# hybrid.net
KiCad netlist of a schematic drawn in EAGLE
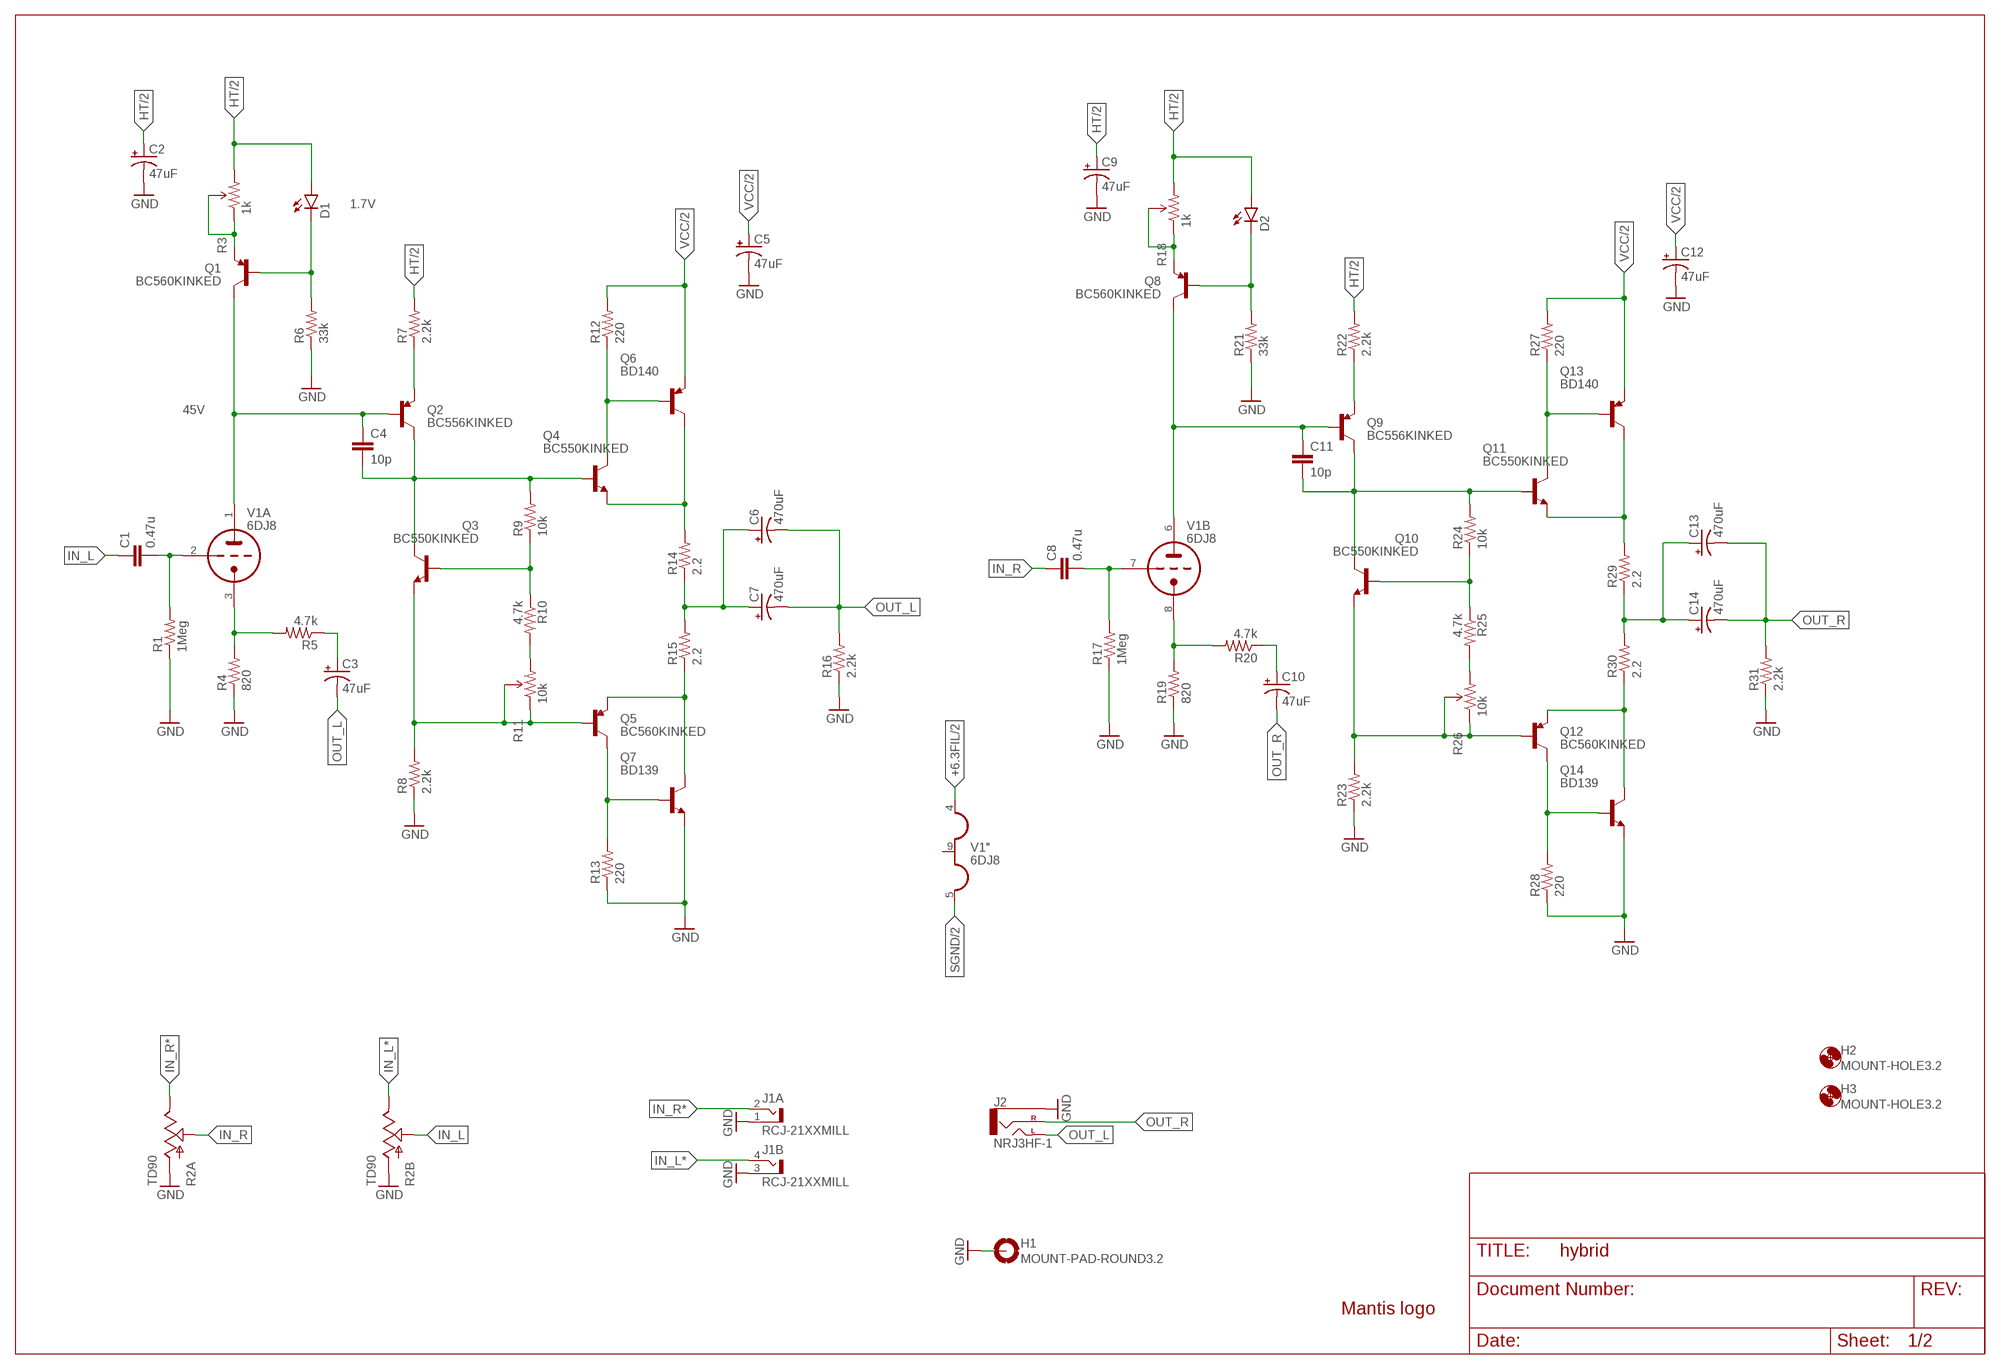
[diagram p0: schematic, sheet 1]
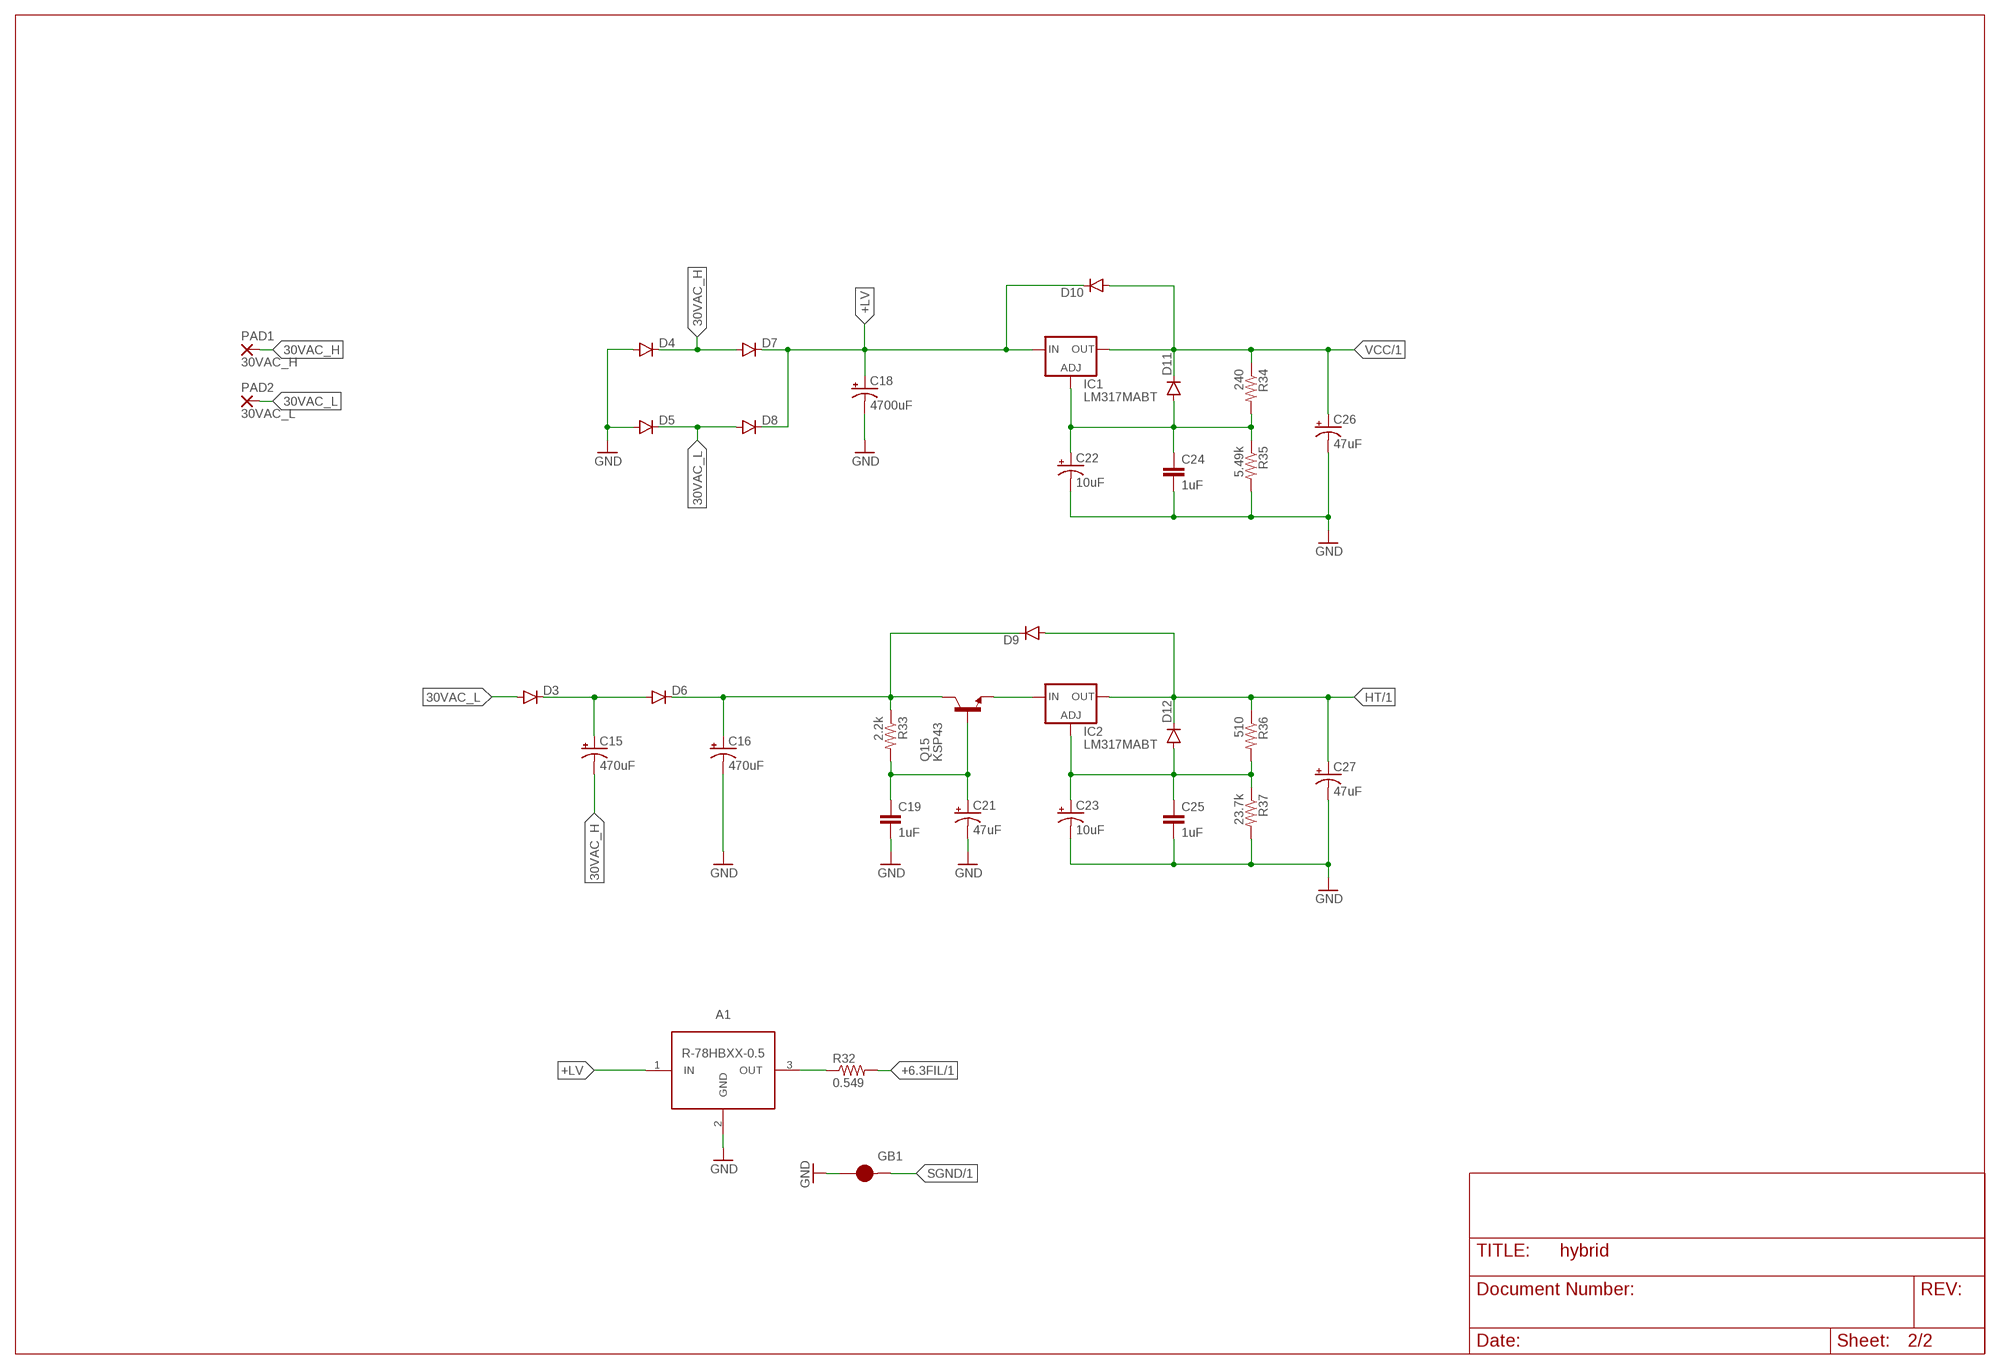
[diagram p1: schematic, sheet 2]

(export (version "E")
  (design (tool "Eeschema 10.0.6"))
  (components
    (comp (ref "A1")
      (value "R-78HBXX-0.5")
      (footprint "eagle-import:R-78HB")
      (libsource (lib "eagle-import") (part "R-78HBXX-0.5"))
    )
    (comp (ref "C15")
      (value "470uF")
      (footprint "eagle-import:CPOL-RADIAL-16_7.5")
      (libsource (lib "eagle-import") (part "CAP_POLPTH-16/7.5"))
    )
    (comp (ref "C16")
      (value "470uF")
      (footprint "eagle-import:CPOL-RADIAL-16_7.5")
      (libsource (lib "eagle-import") (part "CAP_POLPTH-16/7.5"))
    )
    (comp (ref "C18")
      (value "4700uF")
      (footprint "eagle-import:CPOL-RADIAL-22_10")
      (libsource (lib "eagle-import") (part "CAP_POLPTH-22/10"))
    )
    (comp (ref "C19")
      (value "1uF")
      (footprint "eagle-import:CAP-PTH-SMALL")
      (libsource (lib "eagle-import") (part "CAPPTH"))
    )
    (comp (ref "C21")
      (value "47uF")
      (footprint "eagle-import:CPOL-RADIAL-12_5")
      (libsource (lib "eagle-import") (part "CAP_POLPTH-12/5"))
    )
    (comp (ref "C22")
      (value "10uF")
      (footprint "eagle-import:CPOL-RADIAL-5_2.5")
      (libsource (lib "eagle-import") (part "CAP_POLPTH-5/2.5"))
    )
    (comp (ref "C23")
      (value "10uF")
      (footprint "eagle-import:CPOL-RADIAL-6.5_2.5")
      (libsource (lib "eagle-import") (part "CAP_POLPTH-6.5/2.5"))
    )
    (comp (ref "C24")
      (value "1uF")
      (footprint "eagle-import:CAP-PTH-SMALL")
      (libsource (lib "eagle-import") (part "CAPPTH"))
    )
    (comp (ref "C25")
      (value "1uF")
      (footprint "eagle-import:CAP-PTH-SMALL")
      (libsource (lib "eagle-import") (part "CAPPTH"))
    )
    (comp (ref "C26")
      (value "47uF")
      (footprint "eagle-import:CPOL-RADIAL-8_3.5")
      (libsource (lib "eagle-import") (part "CAP_POLPTH-8/3.5"))
    )
    (comp (ref "C27")
      (value "47uF")
      (footprint "eagle-import:CPOL-RADIAL-8_3.5")
      (libsource (lib "eagle-import") (part "CAP_POLPTH-8/3.5"))
    )
    (comp (ref "D3")
      (value "DIODEPTH")
      (footprint "eagle-import:DIODE-1N4001")
      (libsource (lib "eagle-import") (part "DIODEPTH"))
    )
    (comp (ref "D4")
      (value "DIODEPTH")
      (footprint "eagle-import:DIODE-1N4001")
      (libsource (lib "eagle-import") (part "DIODEPTH"))
    )
    (comp (ref "D5")
      (value "DIODEPTH")
      (footprint "eagle-import:DIODE-1N4001")
      (libsource (lib "eagle-import") (part "DIODEPTH"))
    )
    (comp (ref "D6")
      (value "DIODEPTH")
      (footprint "eagle-import:DIODE-1N4001")
      (libsource (lib "eagle-import") (part "DIODEPTH"))
    )
    (comp (ref "D7")
      (value "DIODEPTH")
      (footprint "eagle-import:DIODE-1N4001")
      (libsource (lib "eagle-import") (part "DIODEPTH"))
    )
    (comp (ref "D8")
      (value "DIODEPTH")
      (footprint "eagle-import:DIODE-1N4001")
      (libsource (lib "eagle-import") (part "DIODEPTH"))
    )
    (comp (ref "D9")
      (value "DIODEPTH")
      (footprint "eagle-import:DIODE-1N4001")
      (libsource (lib "eagle-import") (part "DIODEPTH"))
    )
    (comp (ref "D10")
      (value "DIODEPTH")
      (footprint "eagle-import:DIODE-1N4001")
      (libsource (lib "eagle-import") (part "DIODEPTH"))
    )
    (comp (ref "D11")
      (value "DIODEPTH")
      (footprint "eagle-import:DIODE-1N4001")
      (libsource (lib "eagle-import") (part "DIODEPTH"))
    )
    (comp (ref "D12")
      (value "DIODEPTH")
      (footprint "eagle-import:DIODE-1N4001")
      (libsource (lib "eagle-import") (part "DIODEPTH"))
    )
    (comp (ref "GB1")
      (value "COPPER-BRIDGESM")
      (footprint "eagle-import:COPPER-BRIDGE-SM")
      (libsource (lib "eagle-import") (part "COPPER-BRIDGESM"))
    )
    (comp (ref "IC1")
      (value "LM317MABT")
      (footprint "eagle-import:TO220L1")
      (libsource (lib "eagle-import") (part "LM317?MABT"))
    )
    (comp (ref "IC2")
      (value "LM317MABT")
      (footprint "eagle-import:TO220L1")
      (libsource (lib "eagle-import") (part "LM317?MABT"))
    )
    (comp (ref "PAD1")
      (value "30VAC_H")
      (footprint "eagle-import:3,81_1,4")
      (libsource (lib "eagle-import") (part "3,81/1,4"))
    )
    (comp (ref "PAD2")
      (value "30VAC_L")
      (footprint "eagle-import:3,81_1,4")
      (libsource (lib "eagle-import") (part "3,81/1,4"))
    )
    (comp (ref "Q15")
      (value "KSP43")
      (footprint "eagle-import:TO-92")
      (libsource (lib "eagle-import") (part "KSP43"))
    )
    (comp (ref "R32")
      (value "0.549")
      (footprint "eagle-import:AXIAL-0.5")
      (libsource (lib "eagle-import") (part "my-res_RESISTORPTH-1/2W"))
    )
    (comp (ref "R33")
      (value "2.2k")
      (footprint "eagle-import:AXIAL-0.4")
      (libsource (lib "eagle-import") (part "RESISTORPTH-1/4W"))
    )
    (comp (ref "R34")
      (value "240")
      (footprint "eagle-import:AXIAL-0.4")
      (libsource (lib "eagle-import") (part "RESISTORPTH-1/4W"))
    )
    (comp (ref "R35")
      (value "5.49k")
      (footprint "eagle-import:AXIAL-0.4")
      (libsource (lib "eagle-import") (part "RESISTORPTH-1/4W"))
    )
    (comp (ref "R36")
      (value "510")
      (footprint "eagle-import:AXIAL-0.4")
      (libsource (lib "eagle-import") (part "RESISTORPTH-1/4W"))
    )
    (comp (ref "R37")
      (value "23.7k")
      (footprint "eagle-import:AXIAL-0.4")
      (libsource (lib "eagle-import") (part "RESISTORPTH-1/4W"))
    )
    (comp (ref "C1")
      (value "0.47u")
      (footprint "eagle-import:C5B3.5")
      (libsource (lib "eagle-import") (part "C5/3.5"))
    )
    (comp (ref "C2")
      (value "47uF")
      (footprint "eagle-import:CPOL-RADIAL-8_3.5")
      (libsource (lib "eagle-import") (part "CAP_POLPTH-8/3.5"))
    )
    (comp (ref "C3")
      (value "47uF")
      (footprint "eagle-import:CPOL-RADIAL-8_3.5")
      (libsource (lib "eagle-import") (part "CAP_POLPTH-8/3.5"))
    )
    (comp (ref "C4")
      (value "10p")
      (footprint "eagle-import:CAP-PTH-SMALL")
      (libsource (lib "eagle-import") (part "CAPPTH"))
    )
    (comp (ref "C5")
      (value "47uF")
      (footprint "eagle-import:CPOL-RADIAL-8_3.5")
      (libsource (lib "eagle-import") (part "CAP_POLPTH-8/3.5"))
    )
    (comp (ref "C6")
      (value "470uF")
      (footprint "eagle-import:CPOL-RADIAL-12_5")
      (libsource (lib "eagle-import") (part "CAP_POLPTH-12/5"))
    )
    (comp (ref "C7")
      (value "470uF")
      (footprint "eagle-import:CPOL-RADIAL-12_5")
      (libsource (lib "eagle-import") (part "CAP_POLPTH-12/5"))
    )
    (comp (ref "C8")
      (value "0.47u")
      (footprint "eagle-import:C5B3.5")
      (libsource (lib "eagle-import") (part "C5/3.5"))
    )
    (comp (ref "C9")
      (value "47uF")
      (footprint "eagle-import:CPOL-RADIAL-8_3.5")
      (libsource (lib "eagle-import") (part "CAP_POLPTH-8/3.5"))
    )
    (comp (ref "C10")
      (value "47uF")
      (footprint "eagle-import:CPOL-RADIAL-8_3.5")
      (libsource (lib "eagle-import") (part "CAP_POLPTH-8/3.5"))
    )
    (comp (ref "C11")
      (value "10p")
      (footprint "eagle-import:CAP-PTH-SMALL")
      (libsource (lib "eagle-import") (part "CAPPTH"))
    )
    (comp (ref "C12")
      (value "47uF")
      (footprint "eagle-import:CPOL-RADIAL-8_3.5")
      (libsource (lib "eagle-import") (part "CAP_POLPTH-8/3.5"))
    )
    (comp (ref "C13")
      (value "470uF")
      (footprint "eagle-import:CPOL-RADIAL-12_5")
      (libsource (lib "eagle-import") (part "CAP_POLPTH-12/5"))
    )
    (comp (ref "C14")
      (value "470uF")
      (footprint "eagle-import:CPOL-RADIAL-12_5")
      (libsource (lib "eagle-import") (part "CAP_POLPTH-12/5"))
    )
    (comp (ref "D1")
      (value "LED3MM")
      (footprint "eagle-import:LED3MM")
      (libsource (lib "eagle-import") (part "LED3MM"))
    )
    (comp (ref "D2")
      (value "LED3MM")
      (footprint "eagle-import:LED3MM")
      (libsource (lib "eagle-import") (part "LED3MM"))
    )
    (comp (ref "H1")
      (value "MOUNT-PAD-ROUND3.2")
      (footprint "eagle-import:3,2-PAD")
      (libsource (lib "eagle-import") (part "MOUNT-PAD-ROUND3.2"))
    )
    (comp (ref "H2")
      (value "MOUNT-HOLE3.2")
      (footprint "eagle-import:3,2")
      (libsource (lib "eagle-import") (part "MOUNT-HOLE3.2"))
    )
    (comp (ref "H3")
      (value "MOUNT-HOLE3.2")
      (footprint "eagle-import:3,2")
      (libsource (lib "eagle-import") (part "MOUNT-HOLE3.2"))
    )
    (comp (ref "J1")
      (value "RCJ-21XXMILL")
      (footprint "eagle-import:RCJ-21-MILL")
      (libsource (lib "eagle-import") (part "RCJ-21XXMILL"))
    )
    (comp (ref "J2")
      (value "NRJ3HF-1")
      (footprint "eagle-import:NRJ3HF")
      (libsource (lib "eagle-import") (part "NRJ3HF-1"))
    )
    (comp (ref "LOGO1")
      (value "LOGO-MANTIS")
      (footprint "eagle-import:LOGO-MANTIS")
      (libsource (lib "eagle-import") (part "LOGO-MANTIS"))
    )
    (comp (ref "Q1")
      (value "BC560KINKED")
      (footprint "eagle-import:TO92-BENT")
      (libsource (lib "eagle-import") (part "BC560KINKED"))
    )
    (comp (ref "Q2")
      (value "BC556KINKED")
      (footprint "eagle-import:TO92-BENT")
      (libsource (lib "eagle-import") (part "BC556KINKED"))
    )
    (comp (ref "Q3")
      (value "BC550KINKED")
      (footprint "eagle-import:TO92-BENT")
      (libsource (lib "eagle-import") (part "BC550KINKED"))
    )
    (comp (ref "Q4")
      (value "BC550KINKED")
      (footprint "eagle-import:TO92-BENT")
      (libsource (lib "eagle-import") (part "BC550KINKED"))
    )
    (comp (ref "Q5")
      (value "BC560KINKED")
      (footprint "eagle-import:TO92-BENT")
      (libsource (lib "eagle-import") (part "BC560KINKED"))
    )
    (comp (ref "Q6")
      (value "BD140")
      (footprint "eagle-import:TO126")
      (libsource (lib "eagle-import") (part "BD140"))
    )
    (comp (ref "Q7")
      (value "BD139")
      (footprint "eagle-import:TO126")
      (libsource (lib "eagle-import") (part "BD139"))
    )
    (comp (ref "Q8")
      (value "BC560KINKED")
      (footprint "eagle-import:TO92-BENT")
      (libsource (lib "eagle-import") (part "BC560KINKED"))
    )
    (comp (ref "Q9")
      (value "BC556KINKED")
      (footprint "eagle-import:TO92-BENT")
      (libsource (lib "eagle-import") (part "BC556KINKED"))
    )
    (comp (ref "Q10")
      (value "BC550KINKED")
      (footprint "eagle-import:TO92-BENT")
      (libsource (lib "eagle-import") (part "BC550KINKED"))
    )
    (comp (ref "Q11")
      (value "BC550KINKED")
      (footprint "eagle-import:TO92-BENT")
      (libsource (lib "eagle-import") (part "BC550KINKED"))
    )
    (comp (ref "Q12")
      (value "BC560KINKED")
      (footprint "eagle-import:TO92-BENT")
      (libsource (lib "eagle-import") (part "BC560KINKED"))
    )
    (comp (ref "Q13")
      (value "BD140")
      (footprint "eagle-import:TO126")
      (libsource (lib "eagle-import") (part "BD140"))
    )
    (comp (ref "Q14")
      (value "BD139")
      (footprint "eagle-import:TO126")
      (libsource (lib "eagle-import") (part "BD139"))
    )
    (comp (ref "R1")
      (value "1Meg")
      (footprint "eagle-import:AXIAL-0.4")
      (libsource (lib "eagle-import") (part "RESISTORPTH-1/4W"))
    )
    (comp (ref "R2")
      (value "TD90")
      (footprint "eagle-import:PTD902")
      (libsource (lib "eagle-import") (part "TD90"))
    )
    (comp (ref "R3")
      (value "1k")
      (footprint "eagle-import:3362U-2")
      (libsource (lib "eagle-import") (part "TRIMPOT3362U-2"))
    )
    (comp (ref "R4")
      (value "820")
      (footprint "eagle-import:AXIAL-0.4")
      (libsource (lib "eagle-import") (part "RESISTORPTH-1/4W"))
    )
    (comp (ref "R5")
      (value "4.7k")
      (footprint "eagle-import:AXIAL-0.4")
      (libsource (lib "eagle-import") (part "RESISTORPTH-1/4W"))
    )
    (comp (ref "R6")
      (value "33k")
      (footprint "eagle-import:AXIAL-0.4")
      (libsource (lib "eagle-import") (part "RESISTORPTH-1/4W"))
    )
    (comp (ref "R7")
      (value "2.2k")
      (footprint "eagle-import:AXIAL-0.4")
      (libsource (lib "eagle-import") (part "RESISTORPTH-1/4W"))
    )
    (comp (ref "R8")
      (value "2.2k")
      (footprint "eagle-import:AXIAL-0.4")
      (libsource (lib "eagle-import") (part "RESISTORPTH-1/4W"))
    )
    (comp (ref "R9")
      (value "10k")
      (footprint "eagle-import:AXIAL-0.4")
      (libsource (lib "eagle-import") (part "RESISTORPTH-1/4W"))
    )
    (comp (ref "R10")
      (value "4.7k")
      (footprint "eagle-import:AXIAL-0.4")
      (libsource (lib "eagle-import") (part "RESISTORPTH-1/4W"))
    )
    (comp (ref "R11")
      (value "10k")
      (footprint "eagle-import:3362U-2")
      (libsource (lib "eagle-import") (part "TRIMPOT3362U-2"))
    )
    (comp (ref "R12")
      (value "220")
      (footprint "eagle-import:AXIAL-0.4")
      (libsource (lib "eagle-import") (part "RESISTORPTH-1/4W"))
    )
    (comp (ref "R13")
      (value "220")
      (footprint "eagle-import:AXIAL-0.4")
      (libsource (lib "eagle-import") (part "RESISTORPTH-1/4W"))
    )
    (comp (ref "R14")
      (value "2.2")
      (footprint "eagle-import:AXIAL-0.5")
      (libsource (lib "eagle-import") (part "RESISTORPTH-1/2W"))
    )
    (comp (ref "R15")
      (value "2.2")
      (footprint "eagle-import:AXIAL-0.5")
      (libsource (lib "eagle-import") (part "RESISTORPTH-1/2W"))
    )
    (comp (ref "R16")
      (value "2.2k")
      (footprint "eagle-import:AXIAL-0.4")
      (libsource (lib "eagle-import") (part "RESISTORPTH-1/4W"))
    )
    (comp (ref "R17")
      (value "1Meg")
      (footprint "eagle-import:AXIAL-0.4")
      (libsource (lib "eagle-import") (part "RESISTORPTH-1/4W"))
    )
    (comp (ref "R18")
      (value "1k")
      (footprint "eagle-import:3362U-2")
      (libsource (lib "eagle-import") (part "TRIMPOT3362U-2"))
    )
    (comp (ref "R19")
      (value "820")
      (footprint "eagle-import:AXIAL-0.4")
      (libsource (lib "eagle-import") (part "RESISTORPTH-1/4W"))
    )
    (comp (ref "R20")
      (value "4.7k")
      (footprint "eagle-import:AXIAL-0.4")
      (libsource (lib "eagle-import") (part "RESISTORPTH-1/4W"))
    )
    (comp (ref "R21")
      (value "33k")
      (footprint "eagle-import:AXIAL-0.4")
      (libsource (lib "eagle-import") (part "RESISTORPTH-1/4W"))
    )
    (comp (ref "R22")
      (value "2.2k")
      (footprint "eagle-import:AXIAL-0.4")
      (libsource (lib "eagle-import") (part "RESISTORPTH-1/4W"))
    )
    (comp (ref "R23")
      (value "2.2k")
      (footprint "eagle-import:AXIAL-0.4")
      (libsource (lib "eagle-import") (part "RESISTORPTH-1/4W"))
    )
    (comp (ref "R24")
      (value "10k")
      (footprint "eagle-import:AXIAL-0.4")
      (libsource (lib "eagle-import") (part "RESISTORPTH-1/4W"))
    )
    (comp (ref "R25")
      (value "4.7k")
      (footprint "eagle-import:AXIAL-0.4")
      (libsource (lib "eagle-import") (part "RESISTORPTH-1/4W"))
    )
    (comp (ref "R26")
      (value "10k")
      (footprint "eagle-import:3362U-2")
      (libsource (lib "eagle-import") (part "TRIMPOT3362U-2"))
    )
    (comp (ref "R27")
      (value "220")
      (footprint "eagle-import:AXIAL-0.4")
      (libsource (lib "eagle-import") (part "RESISTORPTH-1/4W"))
    )
    (comp (ref "R28")
      (value "220")
      (footprint "eagle-import:AXIAL-0.4")
      (libsource (lib "eagle-import") (part "RESISTORPTH-1/4W"))
    )
    (comp (ref "R29")
      (value "2.2")
      (footprint "eagle-import:AXIAL-0.5")
      (libsource (lib "eagle-import") (part "RESISTORPTH-1/2W"))
    )
    (comp (ref "R30")
      (value "2.2")
      (footprint "eagle-import:AXIAL-0.5")
      (libsource (lib "eagle-import") (part "RESISTORPTH-1/2W"))
    )
    (comp (ref "R31")
      (value "2.2k")
      (footprint "eagle-import:AXIAL-0.4")
      (libsource (lib "eagle-import") (part "RESISTORPTH-1/4W"))
    )
    (comp (ref "V1")
      (value "6DJ8")
      (footprint "eagle-import:NOVAL")
      (libsource (lib "eagle-import") (part "6DJ8-P"))
    )
  )
  (nets
    (net (code "1") (name "+6.3FIL") (class "Default")
      (node (ref "R32") (pin "P$2") (pinfunction "2_P$2") (pintype "passive"))
      (node (ref "V1") (pin "4") (pinfunction "H1_4") (pintype "passive"))
    )
    (net (code "2") (name "+LV") (class "Default")
      (node (ref "A1") (pin "1") (pinfunction "IN_1") (pintype "bidirectional"))
      (node (ref "C18") (pin "1") (pinfunction "+_1") (pintype "passive"))
      (node (ref "D10") (pin "C") (pinfunction "C_C") (pintype "passive"))
      (node (ref "D7") (pin "C") (pinfunction "C_C") (pintype "passive"))
      (node (ref "D8") (pin "C") (pinfunction "C_C") (pintype "passive"))
      (node (ref "IC1") (pin "3") (pinfunction "IN_3") (pintype "input"))
    )
    (net (code "3") (name "30VAC_H") (class "Default")
      (node (ref "C15") (pin "2") (pinfunction "-_2") (pintype "passive"))
      (node (ref "D4") (pin "C") (pinfunction "C_C") (pintype "passive"))
      (node (ref "D7") (pin "A") (pinfunction "A_A") (pintype "passive"))
      (node (ref "PAD1") (pin "1") (pinfunction "P_1") (pintype "passive"))
    )
    (net (code "4") (name "30VAC_L") (class "Default")
      (node (ref "D3") (pin "A") (pinfunction "A_A") (pintype "passive"))
      (node (ref "D5") (pin "C") (pinfunction "C_C") (pintype "passive"))
      (node (ref "D8") (pin "A") (pinfunction "A_A") (pintype "passive"))
      (node (ref "PAD2") (pin "1") (pinfunction "P_1") (pintype "passive"))
    )
    (net (code "5") (name "GND") (class "Default")
      (node (ref "A1") (pin "2") (pinfunction "GND_2") (pintype "bidirectional"))
      (node (ref "C12") (pin "2") (pinfunction "-_2") (pintype "passive"))
      (node (ref "C16") (pin "2") (pinfunction "-_2") (pintype "passive"))
      (node (ref "C18") (pin "2") (pinfunction "-_2") (pintype "passive"))
      (node (ref "C19") (pin "2") (pinfunction "2_2") (pintype "passive"))
      (node (ref "C2") (pin "2") (pinfunction "-_2") (pintype "passive"))
      (node (ref "C21") (pin "-") (pinfunction "-_-") (pintype "passive"))
      (node (ref "C22") (pin "2") (pinfunction "-_2") (pintype "passive"))
      (node (ref "C23") (pin "2") (pinfunction "-_2") (pintype "passive"))
      (node (ref "C24") (pin "2") (pinfunction "2_2") (pintype "passive"))
      (node (ref "C25") (pin "2") (pinfunction "2_2") (pintype "passive"))
      (node (ref "C26") (pin "2") (pinfunction "-_2") (pintype "passive"))
      (node (ref "C27") (pin "2") (pinfunction "-_2") (pintype "passive"))
      (node (ref "C5") (pin "2") (pinfunction "-_2") (pintype "passive"))
      (node (ref "C9") (pin "2") (pinfunction "-_2") (pintype "passive"))
      (node (ref "D4") (pin "A") (pinfunction "A_A") (pintype "passive"))
      (node (ref "D5") (pin "A") (pinfunction "A_A") (pintype "passive"))
      (node (ref "GB1") (pin "1") (pinfunction "1_1") (pintype "passive"))
      (node (ref "H1") (pin "B3,2") (pinfunction "MOUNT_B3,2") (pintype "passive"))
      (node (ref "J1") (pin "1") (pinfunction "S_1") (pintype "passive"))
      (node (ref "J1") (pin "3") (pinfunction "S_3") (pintype "passive"))
      (node (ref "J2") (pin "S") (pinfunction "SLEEVE_S") (pintype "bidirectional"))
      (node (ref "Q14") (pin "1") (pinfunction "E_1") (pintype "passive"))
      (node (ref "Q7") (pin "1") (pinfunction "E_1") (pintype "passive"))
      (node (ref "R1") (pin "P$1") (pinfunction "1_P$1") (pintype "passive"))
      (node (ref "R13") (pin "P$1") (pinfunction "1_P$1") (pintype "passive"))
      (node (ref "R16") (pin "P$1") (pinfunction "1_P$1") (pintype "passive"))
      (node (ref "R17") (pin "P$1") (pinfunction "1_P$1") (pintype "passive"))
      (node (ref "R19") (pin "P$1") (pinfunction "1_P$1") (pintype "passive"))
      (node (ref "R2") (pin "R1.1") (pinfunction "A_R1.1") (pintype "passive"))
      (node (ref "R2") (pin "R2.1") (pinfunction "A_R2.1") (pintype "passive"))
      (node (ref "R21") (pin "P$1") (pinfunction "1_P$1") (pintype "passive"))
      (node (ref "R23") (pin "P$1") (pinfunction "1_P$1") (pintype "passive"))
      (node (ref "R28") (pin "P$1") (pinfunction "1_P$1") (pintype "passive"))
      (node (ref "R31") (pin "P$1") (pinfunction "1_P$1") (pintype "passive"))
      (node (ref "R35") (pin "P$2") (pinfunction "2_P$2") (pintype "passive"))
      (node (ref "R37") (pin "P$2") (pinfunction "2_P$2") (pintype "passive"))
      (node (ref "R4") (pin "P$1") (pinfunction "1_P$1") (pintype "passive"))
      (node (ref "R6") (pin "P$1") (pinfunction "1_P$1") (pintype "passive"))
      (node (ref "R8") (pin "P$1") (pinfunction "1_P$1") (pintype "passive"))
    )
    (net (code "6") (name "HT") (class "Default")
      (node (ref "C2") (pin "1") (pinfunction "+_1") (pintype "passive"))
      (node (ref "C27") (pin "1") (pinfunction "+_1") (pintype "passive"))
      (node (ref "C9") (pin "1") (pinfunction "+_1") (pintype "passive"))
      (node (ref "D1") (pin "A") (pinfunction "A_A") (pintype "passive"))
      (node (ref "D12") (pin "C") (pinfunction "C_C") (pintype "passive"))
      (node (ref "D2") (pin "A") (pinfunction "A_A") (pintype "passive"))
      (node (ref "D9") (pin "A") (pinfunction "A_A") (pintype "passive"))
      (node (ref "IC2") (pin "2") (pinfunction "OUT_2") (pintype "passive"))
      (node (ref "R18") (pin "3") (pinfunction "CW_3") (pintype "passive"))
      (node (ref "R22") (pin "P$2") (pinfunction "2_P$2") (pintype "passive"))
      (node (ref "R3") (pin "3") (pinfunction "CW_3") (pintype "passive"))
      (node (ref "R36") (pin "P$1") (pinfunction "1_P$1") (pintype "passive"))
      (node (ref "R7") (pin "P$2") (pinfunction "2_P$2") (pintype "passive"))
    )
    (net (code "7") (name "IN_L") (class "Default")
      (node (ref "C1") (pin "1") (pinfunction "1_1") (pintype "passive"))
      (node (ref "R2") (pin "R2.2") (pinfunction "S_R2.2") (pintype "passive"))
    )
    (net (code "8") (name "IN_L*") (class "Default")
      (node (ref "J1") (pin "4") (pinfunction "T_4") (pintype "passive"))
      (node (ref "R2") (pin "R2.3") (pinfunction "E_R2.3") (pintype "passive"))
    )
    (net (code "9") (name "IN_R") (class "Default")
      (node (ref "C8") (pin "1") (pinfunction "1_1") (pintype "passive"))
      (node (ref "R2") (pin "R1.2") (pinfunction "S_R1.2") (pintype "passive"))
    )
    (net (code "10") (name "IN_R*") (class "Default")
      (node (ref "J1") (pin "2") (pinfunction "T_2") (pintype "passive"))
      (node (ref "R2") (pin "R1.3") (pinfunction "E_R1.3") (pintype "passive"))
    )
    (net (code "11") (name "Net-(A1-OUT)") (class "Default")
      (node (ref "A1") (pin "3") (pinfunction "OUT_3") (pintype "bidirectional"))
      (node (ref "R32") (pin "P$1") (pinfunction "1_P$1") (pintype "passive"))
    )
    (net (code "12") (name "Net-(C3-+)") (class "Default")
      (node (ref "C3") (pin "1") (pinfunction "+_1") (pintype "passive"))
      (node (ref "R5") (pin "P$1") (pinfunction "1_P$1") (pintype "passive"))
    )
    (net (code "13") (name "Net-(C10-+)") (class "Default")
      (node (ref "C10") (pin "1") (pinfunction "+_1") (pintype "passive"))
      (node (ref "R20") (pin "P$1") (pinfunction "1_P$1") (pintype "passive"))
    )
    (net (code "14") (name "Net-(C15-+)") (class "Default")
      (node (ref "C15") (pin "1") (pinfunction "+_1") (pintype "passive"))
      (node (ref "D3") (pin "C") (pinfunction "C_C") (pintype "passive"))
      (node (ref "D6") (pin "A") (pinfunction "A_A") (pintype "passive"))
    )
    (net (code "15") (name "Net-(C16-+)") (class "Default")
      (node (ref "C16") (pin "1") (pinfunction "+_1") (pintype "passive"))
      (node (ref "D6") (pin "C") (pinfunction "C_C") (pintype "passive"))
      (node (ref "D9") (pin "C") (pinfunction "C_C") (pintype "passive"))
      (node (ref "Q15") (pin "3") (pinfunction "C_3") (pintype "passive"))
      (node (ref "R33") (pin "P$1") (pinfunction "1_P$1") (pintype "passive"))
    )
    (net (code "16") (name "Net-(C22-+)") (class "Default")
      (node (ref "C22") (pin "1") (pinfunction "+_1") (pintype "passive"))
      (node (ref "C24") (pin "1") (pinfunction "1_1") (pintype "passive"))
      (node (ref "D11") (pin "A") (pinfunction "A_A") (pintype "passive"))
      (node (ref "IC1") (pin "1") (pinfunction "ADJ_1") (pintype "input"))
      (node (ref "R34") (pin "P$2") (pinfunction "2_P$2") (pintype "passive"))
      (node (ref "R35") (pin "P$1") (pinfunction "1_P$1") (pintype "passive"))
    )
    (net (code "17") (name "Net-(C23-+)") (class "Default")
      (node (ref "C23") (pin "1") (pinfunction "+_1") (pintype "passive"))
      (node (ref "C25") (pin "1") (pinfunction "1_1") (pintype "passive"))
      (node (ref "D12") (pin "A") (pinfunction "A_A") (pintype "passive"))
      (node (ref "IC2") (pin "1") (pinfunction "ADJ_1") (pintype "input"))
      (node (ref "R36") (pin "P$2") (pinfunction "2_P$2") (pintype "passive"))
      (node (ref "R37") (pin "P$1") (pinfunction "1_P$1") (pintype "passive"))
    )
    (net (code "18") (name "Net-(D1-C)") (class "Default")
      (node (ref "D1") (pin "K") (pinfunction "C_K") (pintype "passive"))
      (node (ref "Q1") (pin "2") (pinfunction "B_2") (pintype "passive"))
      (node (ref "R6") (pin "P$2") (pinfunction "2_P$2") (pintype "passive"))
    )
    (net (code "19") (name "Net-(D2-C)") (class "Default")
      (node (ref "D2") (pin "K") (pinfunction "C_K") (pintype "passive"))
      (node (ref "Q8") (pin "2") (pinfunction "B_2") (pintype "passive"))
      (node (ref "R21") (pin "P$2") (pinfunction "2_P$2") (pintype "passive"))
    )
    (net (code "20") (name "Net-(IC2-IN)") (class "Default")
      (node (ref "IC2") (pin "3") (pinfunction "IN_3") (pintype "input"))
      (node (ref "Q15") (pin "1") (pinfunction "E_1") (pintype "passive"))
    )
    (net (code "21") (name "Net-(Q1-C)") (class "Default")
      (node (ref "C4") (pin "1") (pinfunction "1_1") (pintype "passive"))
      (node (ref "Q1") (pin "1") (pinfunction "C_1") (pintype "passive"))
      (node (ref "Q2") (pin "2") (pinfunction "B_2") (pintype "passive"))
      (node (ref "V1") (pin "1") (pinfunction "TA_1") (pintype "passive"))
    )
    (net (code "22") (name "Net-(Q1-E)") (class "Default")
      (node (ref "Q1") (pin "3") (pinfunction "E_3") (pintype "passive"))
      (node (ref "R3") (pin "1") (pinfunction "CCW_1") (pintype "passive"))
      (node (ref "R3") (pin "2") (pinfunction "WIPER_2") (pintype "passive"))
    )
    (net (code "23") (name "Net-(Q2-C)") (class "Default")
      (node (ref "C4") (pin "2") (pinfunction "2_2") (pintype "passive"))
      (node (ref "Q2") (pin "1") (pinfunction "C_1") (pintype "passive"))
      (node (ref "Q3") (pin "1") (pinfunction "C_1") (pintype "passive"))
      (node (ref "Q4") (pin "2") (pinfunction "B_2") (pintype "passive"))
      (node (ref "R9") (pin "P$2") (pinfunction "2_P$2") (pintype "passive"))
    )
    (net (code "24") (name "Net-(Q2-E)") (class "Default")
      (node (ref "Q2") (pin "3") (pinfunction "E_3") (pintype "passive"))
      (node (ref "R7") (pin "P$1") (pinfunction "1_P$1") (pintype "passive"))
    )
    (net (code "25") (name "Net-(Q3-B)") (class "Default")
      (node (ref "Q3") (pin "2") (pinfunction "B_2") (pintype "passive"))
      (node (ref "R10") (pin "P$1") (pinfunction "1_P$1") (pintype "passive"))
      (node (ref "R9") (pin "P$1") (pinfunction "1_P$1") (pintype "passive"))
    )
    (net (code "26") (name "Net-(Q3-E)") (class "Default")
      (node (ref "Q3") (pin "3") (pinfunction "E_3") (pintype "passive"))
      (node (ref "Q5") (pin "2") (pinfunction "B_2") (pintype "passive"))
      (node (ref "R11") (pin "1") (pinfunction "CCW_1") (pintype "passive"))
      (node (ref "R11") (pin "2") (pinfunction "WIPER_2") (pintype "passive"))
      (node (ref "R8") (pin "P$2") (pinfunction "2_P$2") (pintype "passive"))
    )
    (net (code "27") (name "Net-(Q4-C)") (class "Default")
      (node (ref "Q4") (pin "1") (pinfunction "C_1") (pintype "passive"))
      (node (ref "Q6") (pin "3") (pinfunction "B_3") (pintype "passive"))
      (node (ref "R12") (pin "P$1") (pinfunction "1_P$1") (pintype "passive"))
    )
    (net (code "28") (name "Net-(Q4-E)") (class "Default")
      (node (ref "Q4") (pin "3") (pinfunction "E_3") (pintype "passive"))
      (node (ref "Q6") (pin "2") (pinfunction "C_2") (pintype "passive"))
      (node (ref "R14") (pin "P$2") (pinfunction "2_P$2") (pintype "passive"))
    )
    (net (code "29") (name "Net-(Q5-C)") (class "Default")
      (node (ref "Q5") (pin "1") (pinfunction "C_1") (pintype "passive"))
      (node (ref "Q7") (pin "3") (pinfunction "B_3") (pintype "passive"))
      (node (ref "R13") (pin "P$2") (pinfunction "2_P$2") (pintype "passive"))
    )
    (net (code "30") (name "Net-(Q5-E)") (class "Default")
      (node (ref "Q5") (pin "3") (pinfunction "E_3") (pintype "passive"))
      (node (ref "Q7") (pin "2") (pinfunction "C_2") (pintype "passive"))
      (node (ref "R15") (pin "P$1") (pinfunction "1_P$1") (pintype "passive"))
    )
    (net (code "31") (name "Net-(Q8-C)") (class "Default")
      (node (ref "C11") (pin "1") (pinfunction "1_1") (pintype "passive"))
      (node (ref "Q8") (pin "1") (pinfunction "C_1") (pintype "passive"))
      (node (ref "Q9") (pin "2") (pinfunction "B_2") (pintype "passive"))
      (node (ref "V1") (pin "6") (pinfunction "TA_6") (pintype "passive"))
    )
    (net (code "32") (name "Net-(Q8-E)") (class "Default")
      (node (ref "Q8") (pin "3") (pinfunction "E_3") (pintype "passive"))
      (node (ref "R18") (pin "1") (pinfunction "CCW_1") (pintype "passive"))
      (node (ref "R18") (pin "2") (pinfunction "WIPER_2") (pintype "passive"))
    )
    (net (code "33") (name "Net-(Q9-E)") (class "Default")
      (node (ref "Q9") (pin "3") (pinfunction "E_3") (pintype "passive"))
      (node (ref "R22") (pin "P$1") (pinfunction "1_P$1") (pintype "passive"))
    )
    (net (code "34") (name "Net-(Q10-B)") (class "Default")
      (node (ref "Q10") (pin "2") (pinfunction "B_2") (pintype "passive"))
      (node (ref "R24") (pin "P$1") (pinfunction "1_P$1") (pintype "passive"))
      (node (ref "R25") (pin "P$1") (pinfunction "1_P$1") (pintype "passive"))
    )
    (net (code "35") (name "Net-(Q10-C)") (class "Default")
      (node (ref "C11") (pin "2") (pinfunction "2_2") (pintype "passive"))
      (node (ref "Q10") (pin "1") (pinfunction "C_1") (pintype "passive"))
      (node (ref "Q11") (pin "2") (pinfunction "B_2") (pintype "passive"))
      (node (ref "Q9") (pin "1") (pinfunction "C_1") (pintype "passive"))
      (node (ref "R24") (pin "P$2") (pinfunction "2_P$2") (pintype "passive"))
    )
    (net (code "36") (name "Net-(Q10-E)") (class "Default")
      (node (ref "Q10") (pin "3") (pinfunction "E_3") (pintype "passive"))
      (node (ref "Q12") (pin "2") (pinfunction "B_2") (pintype "passive"))
      (node (ref "R23") (pin "P$2") (pinfunction "2_P$2") (pintype "passive"))
      (node (ref "R26") (pin "1") (pinfunction "CCW_1") (pintype "passive"))
      (node (ref "R26") (pin "2") (pinfunction "WIPER_2") (pintype "passive"))
    )
    (net (code "37") (name "Net-(Q11-C)") (class "Default")
      (node (ref "Q11") (pin "1") (pinfunction "C_1") (pintype "passive"))
      (node (ref "Q13") (pin "3") (pinfunction "B_3") (pintype "passive"))
      (node (ref "R27") (pin "P$1") (pinfunction "1_P$1") (pintype "passive"))
    )
    (net (code "38") (name "Net-(Q11-E)") (class "Default")
      (node (ref "Q11") (pin "3") (pinfunction "E_3") (pintype "passive"))
      (node (ref "Q13") (pin "2") (pinfunction "C_2") (pintype "passive"))
      (node (ref "R29") (pin "P$2") (pinfunction "2_P$2") (pintype "passive"))
    )
    (net (code "39") (name "Net-(Q12-C)") (class "Default")
      (node (ref "Q12") (pin "1") (pinfunction "C_1") (pintype "passive"))
      (node (ref "Q14") (pin "3") (pinfunction "B_3") (pintype "passive"))
      (node (ref "R28") (pin "P$2") (pinfunction "2_P$2") (pintype "passive"))
    )
    (net (code "40") (name "Net-(Q12-E)") (class "Default")
      (node (ref "Q12") (pin "3") (pinfunction "E_3") (pintype "passive"))
      (node (ref "Q14") (pin "2") (pinfunction "C_2") (pintype "passive"))
      (node (ref "R30") (pin "P$1") (pinfunction "1_P$1") (pintype "passive"))
    )
    (net (code "41") (name "Net-(Q15-B)") (class "Default")
      (node (ref "C19") (pin "1") (pinfunction "1_1") (pintype "passive"))
      (node (ref "C21") (pin "+") (pinfunction "+_+") (pintype "passive"))
      (node (ref "Q15") (pin "2") (pinfunction "B_2") (pintype "passive"))
      (node (ref "R33") (pin "P$2") (pinfunction "2_P$2") (pintype "passive"))
    )
    (net (code "42") (name "Net-(R1-2)") (class "Default")
      (node (ref "C1") (pin "2") (pinfunction "2_2") (pintype "passive"))
      (node (ref "R1") (pin "P$2") (pinfunction "2_P$2") (pintype "passive"))
      (node (ref "V1") (pin "2") (pinfunction "TG_2") (pintype "passive"))
    )
    (net (code "43") (name "Net-(R4-2)") (class "Default")
      (node (ref "R4") (pin "P$2") (pinfunction "2_P$2") (pintype "passive"))
      (node (ref "R5") (pin "P$2") (pinfunction "2_P$2") (pintype "passive"))
      (node (ref "V1") (pin "3") (pinfunction "TK_3") (pintype "passive"))
    )
    (net (code "44") (name "Net-(R10-2)") (class "Default")
      (node (ref "R10") (pin "P$2") (pinfunction "2_P$2") (pintype "passive"))
      (node (ref "R11") (pin "3") (pinfunction "CW_3") (pintype "passive"))
    )
    (net (code "45") (name "Net-(R14-1)") (class "Default")
      (node (ref "C6") (pin "+") (pinfunction "+_+") (pintype "passive"))
      (node (ref "C7") (pin "+") (pinfunction "+_+") (pintype "passive"))
      (node (ref "R14") (pin "P$1") (pinfunction "1_P$1") (pintype "passive"))
      (node (ref "R15") (pin "P$2") (pinfunction "2_P$2") (pintype "passive"))
    )
    (net (code "46") (name "Net-(R17-2)") (class "Default")
      (node (ref "C8") (pin "2") (pinfunction "2_2") (pintype "passive"))
      (node (ref "R17") (pin "P$2") (pinfunction "2_P$2") (pintype "passive"))
      (node (ref "V1") (pin "7") (pinfunction "TG_7") (pintype "passive"))
    )
    (net (code "47") (name "Net-(R19-2)") (class "Default")
      (node (ref "R19") (pin "P$2") (pinfunction "2_P$2") (pintype "passive"))
      (node (ref "R20") (pin "P$2") (pinfunction "2_P$2") (pintype "passive"))
      (node (ref "V1") (pin "8") (pinfunction "TK_8") (pintype "passive"))
    )
    (net (code "48") (name "Net-(R25-2)") (class "Default")
      (node (ref "R25") (pin "P$2") (pinfunction "2_P$2") (pintype "passive"))
      (node (ref "R26") (pin "3") (pinfunction "CW_3") (pintype "passive"))
    )
    (net (code "49") (name "Net-(R29-1)") (class "Default")
      (node (ref "C13") (pin "+") (pinfunction "+_+") (pintype "passive"))
      (node (ref "C14") (pin "+") (pinfunction "+_+") (pintype "passive"))
      (node (ref "R29") (pin "P$1") (pinfunction "1_P$1") (pintype "passive"))
      (node (ref "R30") (pin "P$2") (pinfunction "2_P$2") (pintype "passive"))
    )
    (net (code "50") (name "OUT_L") (class "Default")
      (node (ref "C3") (pin "2") (pinfunction "-_2") (pintype "passive"))
      (node (ref "C6") (pin "-") (pinfunction "-_-") (pintype "passive"))
      (node (ref "C7") (pin "-") (pinfunction "-_-") (pintype "passive"))
      (node (ref "J2") (pin "T") (pinfunction "LEFT_T") (pintype "bidirectional"))
      (node (ref "R16") (pin "P$2") (pinfunction "2_P$2") (pintype "passive"))
    )
    (net (code "51") (name "OUT_R") (class "Default")
      (node (ref "C10") (pin "2") (pinfunction "-_2") (pintype "passive"))
      (node (ref "C13") (pin "-") (pinfunction "-_-") (pintype "passive"))
      (node (ref "C14") (pin "-") (pinfunction "-_-") (pintype "passive"))
      (node (ref "J2") (pin "R") (pinfunction "RIGHT_R") (pintype "bidirectional"))
      (node (ref "R31") (pin "P$2") (pinfunction "2_P$2") (pintype "passive"))
    )
    (net (code "52") (name "SGND") (class "Default")
      (node (ref "GB1") (pin "2") (pinfunction "2_2") (pintype "passive"))
      (node (ref "V1") (pin "5") (pinfunction "H3_5") (pintype "passive"))
    )
    (net (code "53") (name "VCC") (class "Default")
      (node (ref "C12") (pin "1") (pinfunction "+_1") (pintype "passive"))
      (node (ref "C26") (pin "1") (pinfunction "+_1") (pintype "passive"))
      (node (ref "C5") (pin "1") (pinfunction "+_1") (pintype "passive"))
      (node (ref "D10") (pin "A") (pinfunction "A_A") (pintype "passive"))
      (node (ref "D11") (pin "C") (pinfunction "C_C") (pintype "passive"))
      (node (ref "IC1") (pin "2") (pinfunction "OUT_2") (pintype "passive"))
      (node (ref "Q13") (pin "1") (pinfunction "E_1") (pintype "passive"))
      (node (ref "Q6") (pin "1") (pinfunction "E_1") (pintype "passive"))
      (node (ref "R12") (pin "P$2") (pinfunction "2_P$2") (pintype "passive"))
      (node (ref "R27") (pin "P$2") (pinfunction "2_P$2") (pintype "passive"))
      (node (ref "R34") (pin "P$1") (pinfunction "1_P$1") (pintype "passive"))
    )
    (net (code "54") (name "unconnected-(V1A-H2-Pad9)") (class "Default")
      (node (ref "V1") (pin "9") (pinfunction "H2_9") (pintype "passive"))
    )
  )
)
